# InkTime.net
KiCad netlist of a schematic drawn in EAGLE
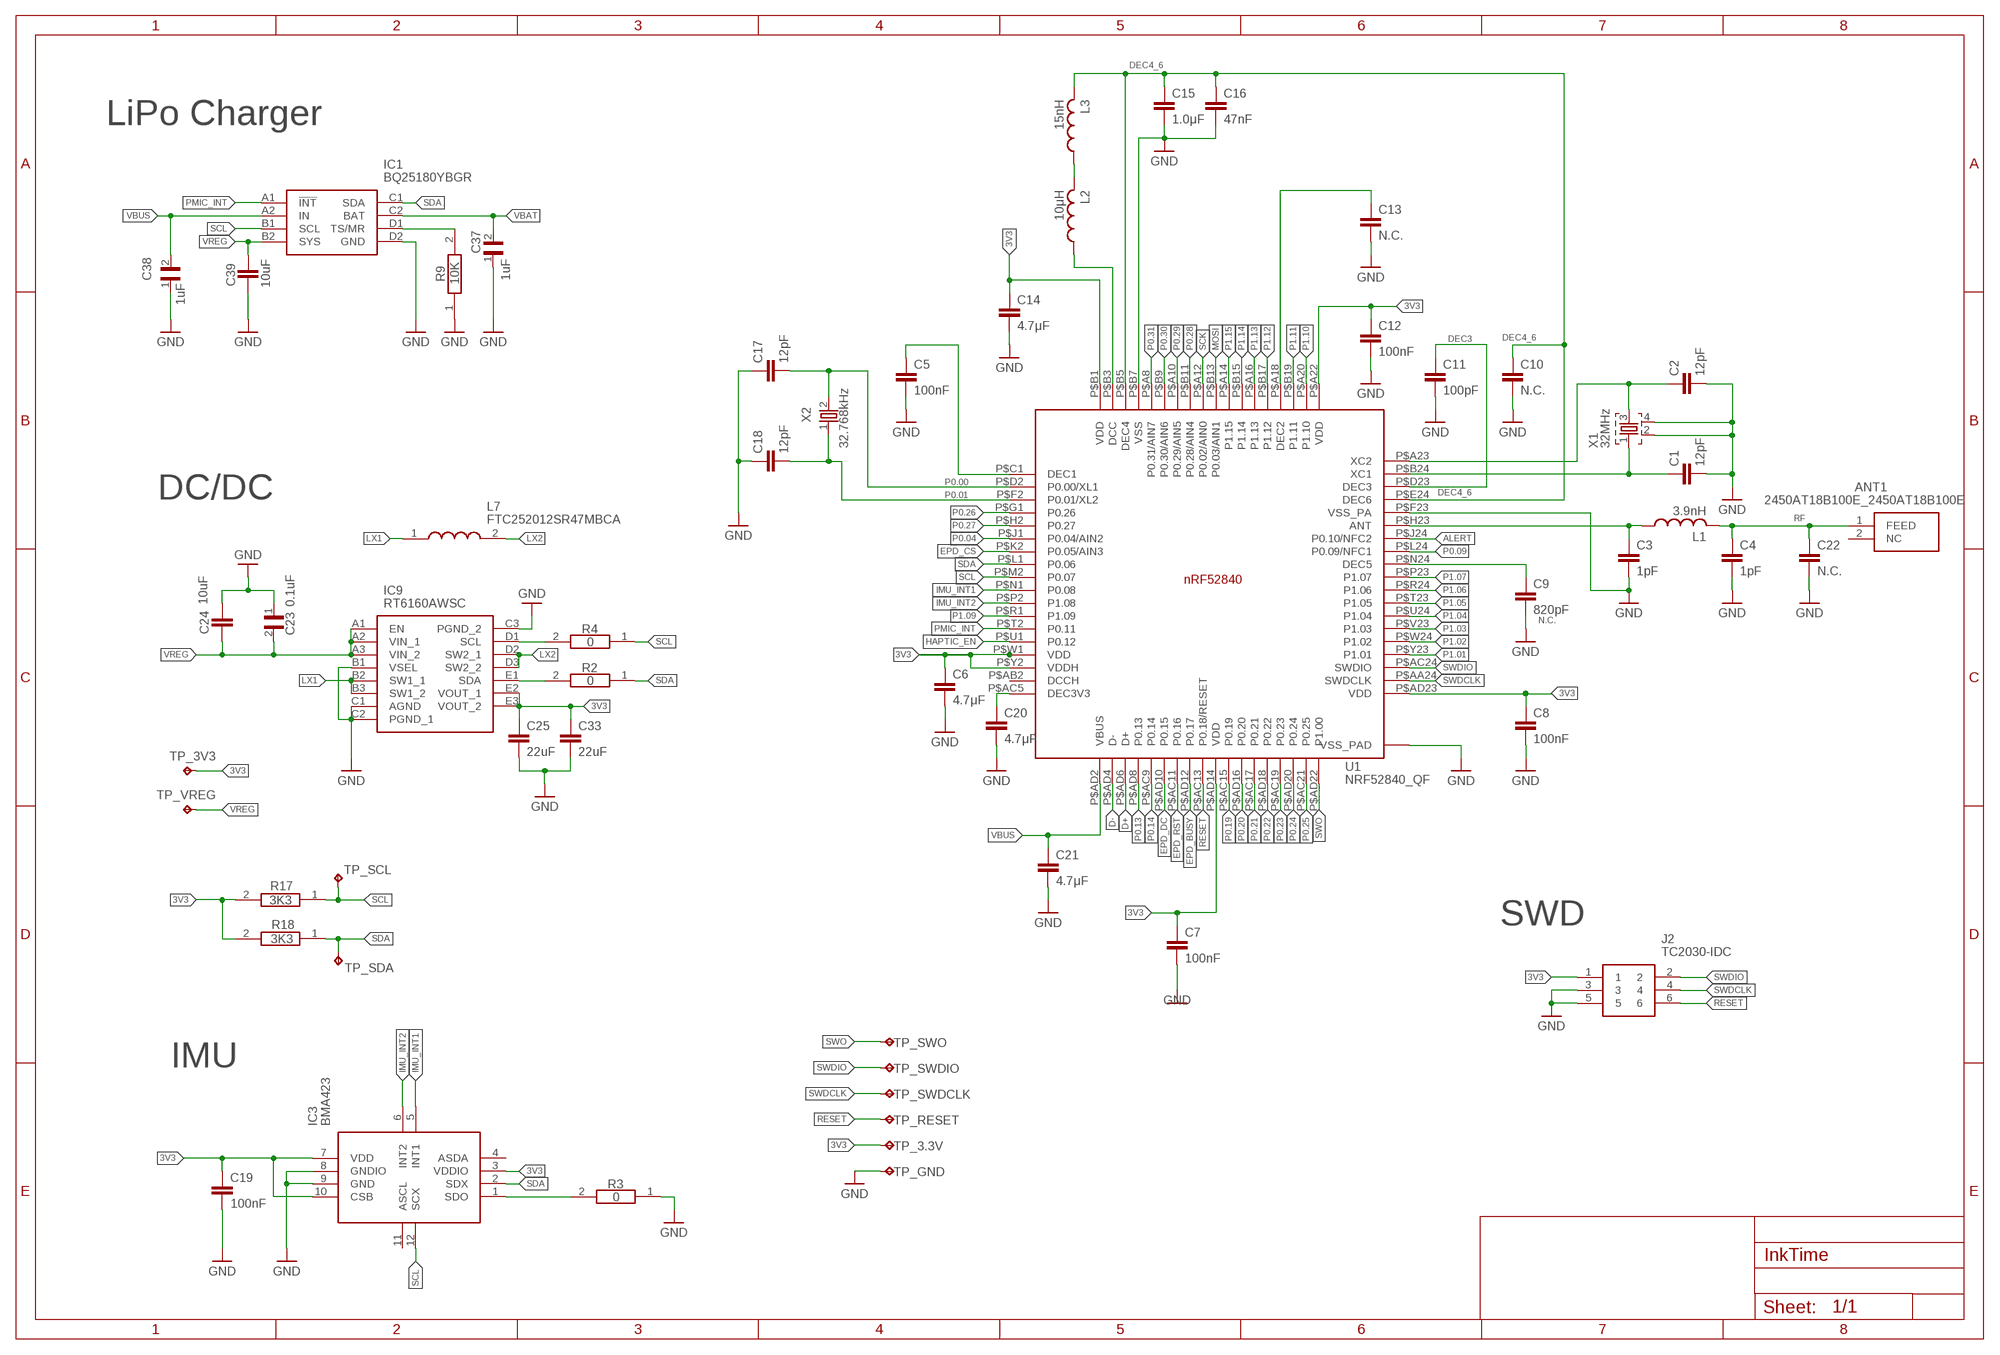
[diagram p0: schematic, sheet 1, part 1 of 2]
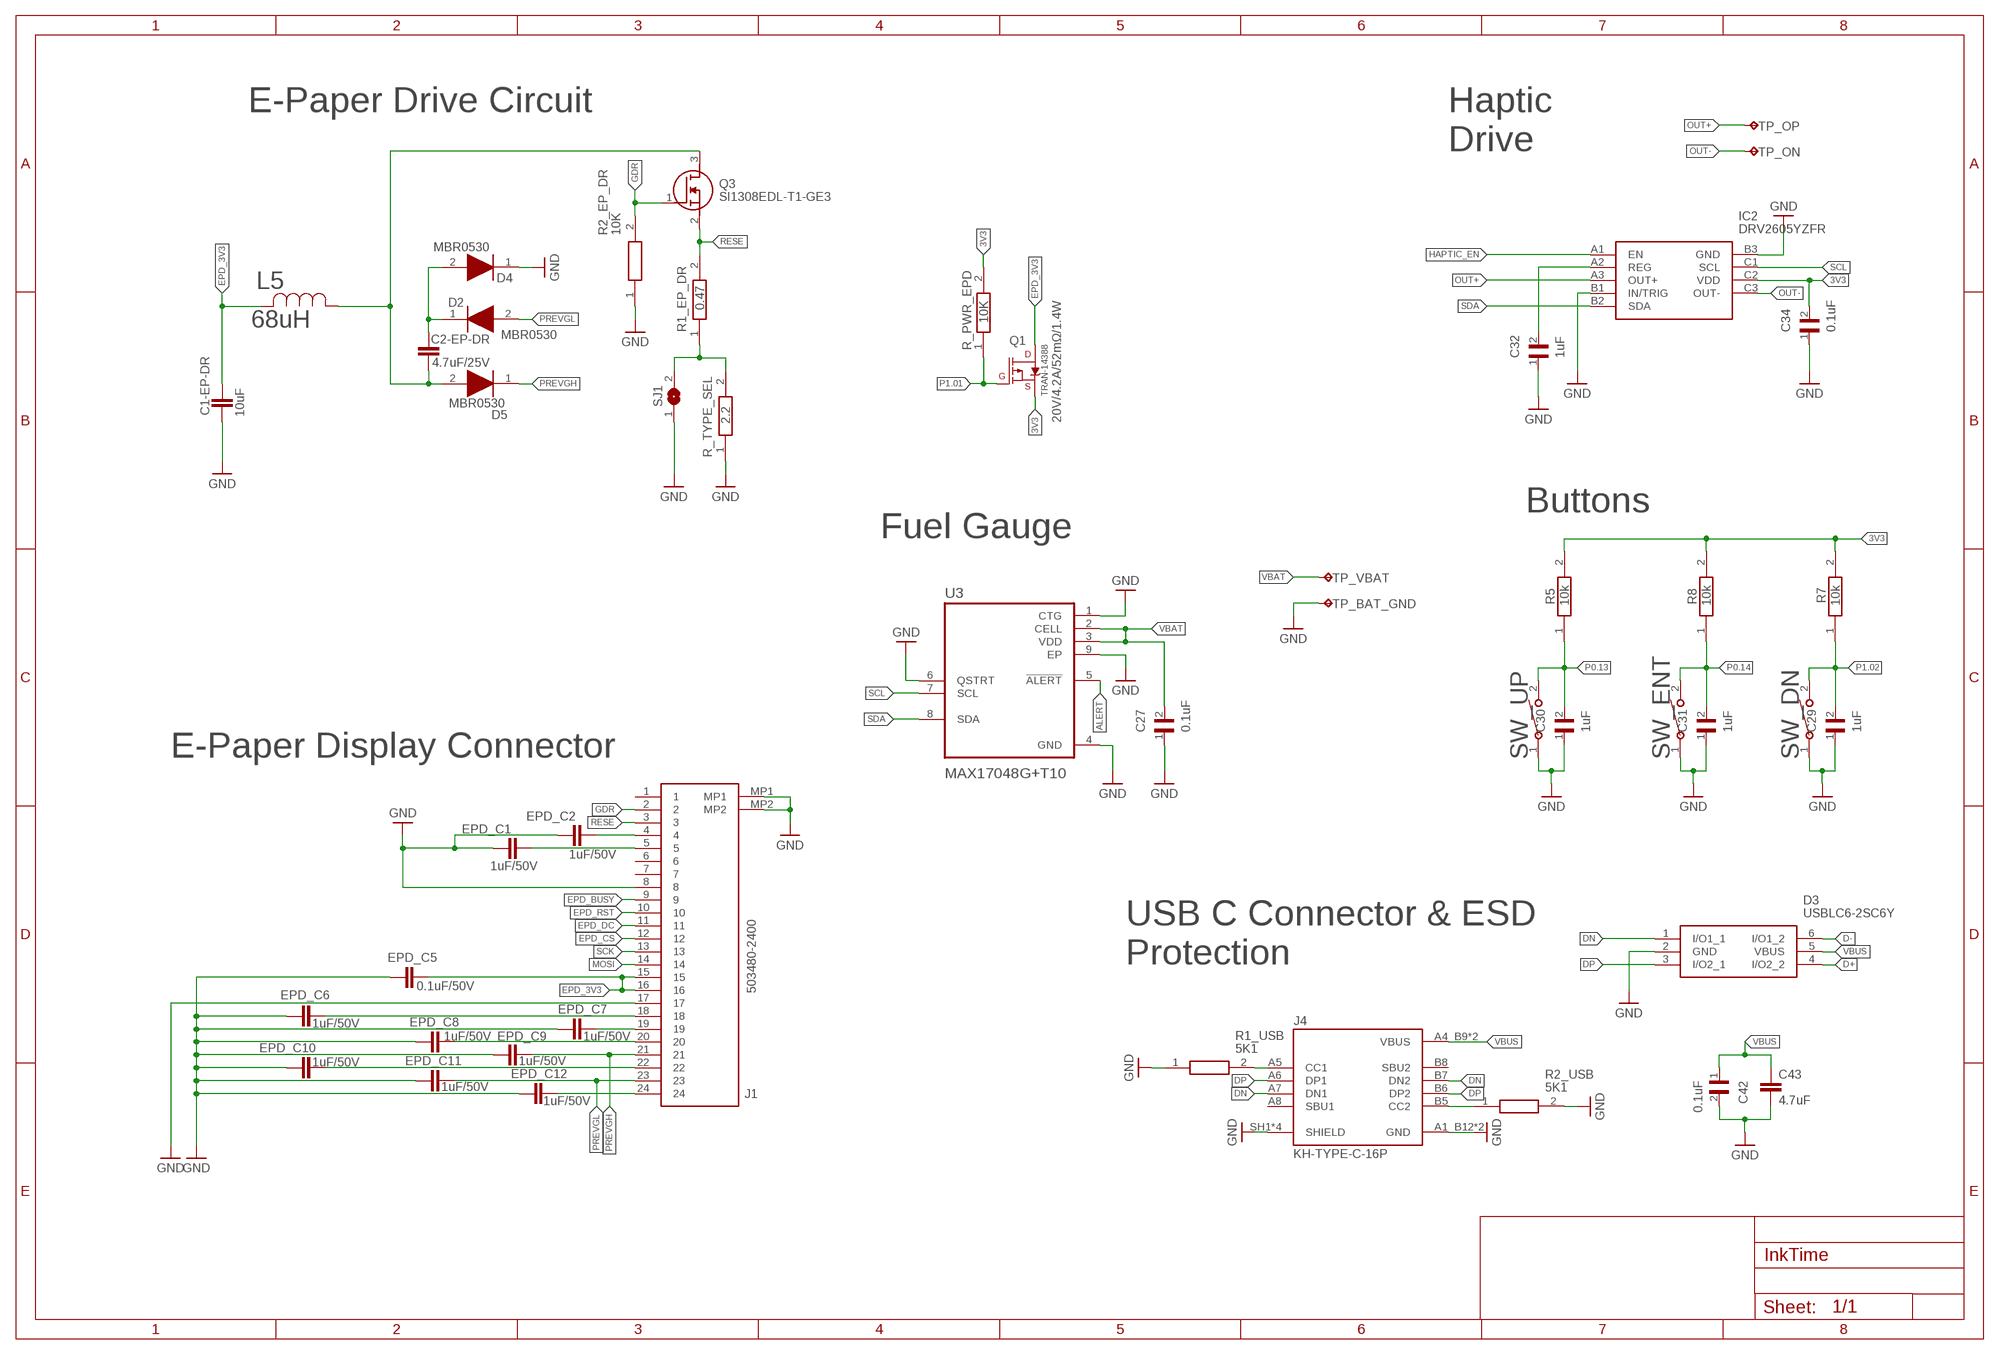
[diagram p1: schematic, sheet 1, part 2 of 2]

(export (version "E")
  (design (tool "Eeschema 10.0.6"))
  (components
    (comp (ref "ANT1")
      (value "2450AT18B100E_2450AT18B100E")
      (footprint "eagle-import:2450AT18B100E_ANTC3216X140N")
      (fields
        (field (name "ARROW_PART_NUMBER") "2450AT18B100E")
        (field (name "MOUSER_PART_NUMBER") "609-2450AT18B100E")
      )
      (libsource (lib "eagle-import") (part "2450AT18B100E_2450AT18B100E"))
    )
    (comp (ref "C1")
      (value "12pF")
      (footprint "eagle-import:NORDIC_NRF_3_RESC0201_L")
      (libsource (lib "eagle-import") (part "NORDIC_NRF_3_CAPACITOR_0201_L"))
    )
    (comp (ref "C1-EP-DR")
      (value "10uF")
      (footprint "eagle-import:NORDIC_NRF_3_RESC0402_L")
      (libsource (lib "eagle-import") (part "NORDIC_NRF_3_CAPACITOR_0402_L"))
    )
    (comp (ref "C2")
      (value "12pF")
      (footprint "eagle-import:NORDIC_NRF_3_RESC0201_L")
      (libsource (lib "eagle-import") (part "NORDIC_NRF_3_CAPACITOR_0201_L"))
    )
    (comp (ref "C2-EP-DR")
      (value "4.7uF/25V")
      (footprint "eagle-import:NORDIC_NRF_3_RESC0402_L")
      (libsource (lib "eagle-import") (part "NORDIC_NRF_3_CAPACITOR_0402_L"))
    )
    (comp (ref "C3")
      (value "1pF")
      (footprint "eagle-import:NORDIC_NRF_3_RESC0201_L")
      (libsource (lib "eagle-import") (part "NORDIC_NRF_3_CAPACITOR_0201_L"))
    )
    (comp (ref "C4")
      (value "1pF")
      (footprint "eagle-import:NORDIC_NRF_3_RESC0201_L")
      (libsource (lib "eagle-import") (part "NORDIC_NRF_3_CAPACITOR_0201_L"))
    )
    (comp (ref "C5")
      (value "100nF")
      (footprint "eagle-import:NORDIC_NRF_3_RESC0201_L")
      (libsource (lib "eagle-import") (part "NORDIC_NRF_3_CAPACITOR_0201_L"))
    )
    (comp (ref "C6")
      (value "4.7μF")
      (footprint "eagle-import:NORDIC_NRF_3_RESC0402_L")
      (libsource (lib "eagle-import") (part "NORDIC_NRF_3_CAPACITOR_0402_L"))
    )
    (comp (ref "C7")
      (value "100nF")
      (footprint "eagle-import:NORDIC_NRF_3_RESC0201_L")
      (libsource (lib "eagle-import") (part "NORDIC_NRF_3_CAPACITOR_0201_L"))
    )
    (comp (ref "C8")
      (value "100nF")
      (footprint "eagle-import:NORDIC_NRF_3_RESC0201_L")
      (libsource (lib "eagle-import") (part "NORDIC_NRF_3_CAPACITOR_0201_L"))
    )
    (comp (ref "C9")
      (value "820pF")
      (footprint "eagle-import:NORDIC_NRF_3_RESC0201_L")
      (fields (field (name "POPULATION") "N.C."))
      (libsource (lib "eagle-import") (part "NORDIC_NRF_3_CAPACITOR_0201_L"))
    )
    (comp (ref "C10")
      (value "N.C.")
      (footprint "eagle-import:NORDIC_NRF_3_RESC0201_L")
      (libsource (lib "eagle-import") (part "NORDIC_NRF_3_CAPACITOR_0201_L"))
    )
    (comp (ref "C11")
      (value "100pF")
      (footprint "eagle-import:NORDIC_NRF_3_RESC0201_L")
      (libsource (lib "eagle-import") (part "NORDIC_NRF_3_CAPACITOR_0201_L"))
    )
    (comp (ref "C12")
      (value "100nF")
      (footprint "eagle-import:NORDIC_NRF_3_RESC0201_L")
      (libsource (lib "eagle-import") (part "NORDIC_NRF_3_CAPACITOR_0201_L"))
    )
    (comp (ref "C13")
      (value "N.C.")
      (footprint "eagle-import:NORDIC_NRF_3_RESC0201_L")
      (libsource (lib "eagle-import") (part "NORDIC_NRF_3_CAPACITOR_0201_L"))
    )
    (comp (ref "C14")
      (value "4.7μF")
      (footprint "eagle-import:NORDIC_NRF_3_RESC0402_L")
      (libsource (lib "eagle-import") (part "NORDIC_NRF_3_CAPACITOR_0402_L"))
    )
    (comp (ref "C15")
      (value "1.0μF")
      (footprint "eagle-import:NORDIC_NRF_3_RESC0402_L")
      (libsource (lib "eagle-import") (part "NORDIC_NRF_3_CAPACITOR_0402_L"))
    )
    (comp (ref "C16")
      (value "47nF")
      (footprint "eagle-import:NORDIC_NRF_3_RESC0201_L")
      (libsource (lib "eagle-import") (part "NORDIC_NRF_3_CAPACITOR_0201_L"))
    )
    (comp (ref "C17")
      (value "12pF")
      (footprint "eagle-import:NORDIC_NRF_3_RESC0201_L")
      (libsource (lib "eagle-import") (part "NORDIC_NRF_3_CAPACITOR_0201_L"))
    )
    (comp (ref "C18")
      (value "12pF")
      (footprint "eagle-import:NORDIC_NRF_3_RESC0201_L")
      (libsource (lib "eagle-import") (part "NORDIC_NRF_3_CAPACITOR_0201_L"))
    )
    (comp (ref "C19")
      (value "100nF")
      (footprint "eagle-import:NORDIC_NRF_3_RESC0201_L")
      (libsource (lib "eagle-import") (part "NORDIC_NRF_3_CAPACITOR_0201_L"))
    )
    (comp (ref "C20")
      (value "4.7μF")
      (footprint "eagle-import:NORDIC_NRF_3_RESC0402_L")
      (libsource (lib "eagle-import") (part "NORDIC_NRF_3_CAPACITOR_0402_L"))
    )
    (comp (ref "C21")
      (value "4.7μF")
      (footprint "eagle-import:NORDIC_NRF_3_RESC0402_L")
      (libsource (lib "eagle-import") (part "NORDIC_NRF_3_CAPACITOR_0402_L"))
    )
    (comp (ref "C22")
      (value "N.C.")
      (footprint "eagle-import:NORDIC_NRF_3_RESC0201_L")
      (libsource (lib "eagle-import") (part "NORDIC_NRF_3_CAPACITOR_0201_L"))
    )
    (comp (ref "C23")
      (value "0.1uF")
      (footprint "eagle-import:GRM011R60J152KE01L_2_CAPC0201X13N")
      (fields (field (name "MF") "Murata") (field (name "MP") "GRM011R60J152KE01L"))
      (libsource (lib "eagle-import") (part "GRM011R60J152KE01L_2_GRM011R60J152KE01L"))
    )
    (comp (ref "C24")
      (value "10uF")
      (footprint "eagle-import:NORDIC_NRF_3_RESC0402_L")
      (libsource (lib "eagle-import") (part "NORDIC_NRF_3_CAPACITOR_0402_L"))
    )
    (comp (ref "C25")
      (value "22uF")
      (footprint "eagle-import:NORDIC_NRF_3_RESC0402_L")
      (libsource (lib "eagle-import") (part "NORDIC_NRF_3_CAPACITOR_0402_L"))
    )
    (comp (ref "C27")
      (value "0.1uF")
      (footprint "eagle-import:GRM011R60J152KE01L_2_CAPC0201X13N")
      (fields (field (name "MF") "Murata") (field (name "MP") "GRM011R60J152KE01L"))
      (libsource (lib "eagle-import") (part "GRM011R60J152KE01L_2_GRM011R60J152KE01L"))
    )
    (comp (ref "C29")
      (value "1uF")
      (footprint "eagle-import:GRM011R60J152KE01L_2_CAPC0201X13N")
      (fields (field (name "MF") "Murata") (field (name "MP") "GRM011R60J152KE01L"))
      (libsource (lib "eagle-import") (part "GRM011R60J152KE01L_2_GRM011R60J152KE01L"))
    )
    (comp (ref "C30")
      (value "1uF")
      (footprint "eagle-import:GRM011R60J152KE01L_2_CAPC0201X13N")
      (fields (field (name "MF") "Murata") (field (name "MP") "GRM011R60J152KE01L"))
      (libsource (lib "eagle-import") (part "GRM011R60J152KE01L_2_GRM011R60J152KE01L"))
    )
    (comp (ref "C31")
      (value "1uF")
      (footprint "eagle-import:GRM011R60J152KE01L_2_CAPC0201X13N")
      (fields (field (name "MF") "Murata") (field (name "MP") "GRM011R60J152KE01L"))
      (libsource (lib "eagle-import") (part "GRM011R60J152KE01L_2_GRM011R60J152KE01L"))
    )
    (comp (ref "C32")
      (value "1uF")
      (footprint "eagle-import:GRM011R60J152KE01L_2_CAPC0201X13N")
      (fields (field (name "MF") "Murata") (field (name "MP") "GRM011R60J152KE01L"))
      (libsource (lib "eagle-import") (part "GRM011R60J152KE01L_2_GRM011R60J152KE01L"))
    )
    (comp (ref "C33")
      (value "22uF")
      (footprint "eagle-import:NORDIC_NRF_3_RESC0402_L")
      (libsource (lib "eagle-import") (part "NORDIC_NRF_3_CAPACITOR_0402_L"))
    )
    (comp (ref "C34")
      (value "0.1uF")
      (footprint "eagle-import:GRM011R60J152KE01L_2_CAPC0201X13N")
      (fields (field (name "MF") "Murata") (field (name "MP") "GRM011R60J152KE01L"))
      (libsource (lib "eagle-import") (part "GRM011R60J152KE01L_2_GRM011R60J152KE01L"))
    )
    (comp (ref "C37")
      (value "1uF")
      (footprint "eagle-import:GRM011R60J152KE01L_2_CAPC0201X13N")
      (fields (field (name "MF") "Murata") (field (name "MP") "GRM011R60J152KE01L"))
      (libsource (lib "eagle-import") (part "GRM011R60J152KE01L_2_GRM011R60J152KE01L"))
    )
    (comp (ref "C38")
      (value "1uF")
      (footprint "eagle-import:GRM011R60J152KE01L_2_CAPC0201X13N")
      (fields (field (name "MF") "Murata") (field (name "MP") "GRM011R60J152KE01L"))
      (libsource (lib "eagle-import") (part "GRM011R60J152KE01L_2_GRM011R60J152KE01L"))
    )
    (comp (ref "C39")
      (value "10uF")
      (footprint "eagle-import:NORDIC_NRF_3_RESC0402_L")
      (libsource (lib "eagle-import") (part "NORDIC_NRF_3_CAPACITOR_0402_L"))
    )
    (comp (ref "C42")
      (value "0.1uF")
      (footprint "eagle-import:GRM011R60J152KE01L_2_CAPC0201X13N")
      (fields (field (name "MF") "Murata") (field (name "MP") "GRM011R60J152KE01L"))
      (libsource (lib "eagle-import") (part "GRM011R60J152KE01L_2_GRM011R60J152KE01L"))
    )
    (comp (ref "C43")
      (value "4.7uF")
      (footprint "eagle-import:NORDIC_NRF_3_RESC0402_L")
      (libsource (lib "eagle-import") (part "NORDIC_NRF_3_CAPACITOR_0402_L"))
    )
    (comp (ref "D2")
      (value "MBR0530")
      (footprint "eagle-import:ESP32_C6_LIBRARY_5_SOD3716X135N")
      (fields (field (name "MF") "ON Semiconductor"))
      (libsource (lib "eagle-import") (part "ESP32_C6_LIBRARY_5_MBR0530"))
    )
    (comp (ref "D3")
      (value "USBLC6-2SC6Y")
      (footprint "eagle-import:ESP32_C6_LIBRARY_3_SOT95P280X145-6N")
      (fields (field (name "MF") "STMicroelectronics"))
      (libsource (lib "eagle-import") (part "ESP32_C6_LIBRARY_3_USBLC6-2SC6Y"))
    )
    (comp (ref "D4")
      (value "MBR0530")
      (footprint "eagle-import:ESP32_C6_LIBRARY_5_SOD3716X135N")
      (fields (field (name "MF") "ON Semiconductor"))
      (libsource (lib "eagle-import") (part "ESP32_C6_LIBRARY_5_MBR0530"))
    )
    (comp (ref "D5")
      (value "MBR0530")
      (footprint "eagle-import:ESP32_C6_LIBRARY_5_SOD3716X135N")
      (fields (field (name "MF") "ON Semiconductor"))
      (libsource (lib "eagle-import") (part "ESP32_C6_LIBRARY_5_MBR0530"))
    )
    (comp (ref "EPD_C1")
      (value "1uF/50V")
      (footprint "eagle-import:NORDIC_NRF_3_RESC0402_L")
      (libsource (lib "eagle-import") (part "NORDIC_NRF_3_CAPACITOR_0402_L"))
    )
    (comp (ref "EPD_C2")
      (value "1uF/50V")
      (footprint "eagle-import:NORDIC_NRF_3_RESC0402_L")
      (libsource (lib "eagle-import") (part "NORDIC_NRF_3_CAPACITOR_0402_L"))
    )
    (comp (ref "EPD_C5")
      (value "0.1uF/50V")
      (footprint "eagle-import:NORDIC_NRF_3_RESC0201_L")
      (libsource (lib "eagle-import") (part "NORDIC_NRF_3_CAPACITOR_0201_L"))
    )
    (comp (ref "EPD_C6")
      (value "1uF/50V")
      (footprint "eagle-import:NORDIC_NRF_3_RESC0402_L")
      (libsource (lib "eagle-import") (part "NORDIC_NRF_3_CAPACITOR_0402_L"))
    )
    (comp (ref "EPD_C7")
      (value "1uF/50V")
      (footprint "eagle-import:NORDIC_NRF_3_RESC0402_L")
      (libsource (lib "eagle-import") (part "NORDIC_NRF_3_CAPACITOR_0402_L"))
    )
    (comp (ref "EPD_C8")
      (value "1uF/50V")
      (footprint "eagle-import:NORDIC_NRF_3_RESC0402_L")
      (libsource (lib "eagle-import") (part "NORDIC_NRF_3_CAPACITOR_0402_L"))
    )
    (comp (ref "EPD_C9")
      (value "1uF/50V")
      (footprint "eagle-import:NORDIC_NRF_3_RESC0402_L")
      (libsource (lib "eagle-import") (part "NORDIC_NRF_3_CAPACITOR_0402_L"))
    )
    (comp (ref "EPD_C10")
      (value "1uF/50V")
      (footprint "eagle-import:NORDIC_NRF_3_RESC0402_L")
      (libsource (lib "eagle-import") (part "NORDIC_NRF_3_CAPACITOR_0402_L"))
    )
    (comp (ref "EPD_C11")
      (value "1uF/50V")
      (footprint "eagle-import:NORDIC_NRF_3_RESC0402_L")
      (libsource (lib "eagle-import") (part "NORDIC_NRF_3_CAPACITOR_0402_L"))
    )
    (comp (ref "EPD_C12")
      (value "1uF/50V")
      (footprint "eagle-import:NORDIC_NRF_3_RESC0402_L")
      (libsource (lib "eagle-import") (part "NORDIC_NRF_3_CAPACITOR_0402_L"))
    )
    (comp (ref "IC1")
      (value "BQ25180YBGR")
      (footprint "eagle-import:BQ25180YBGR_BGA8C40P2X4_100X155X50")
      (fields (field (name "MOUSER_PART_NUMBER") "595-BQ25180YBGR"))
      (libsource (lib "eagle-import") (part "BQ25180YBGR_BQ25180YBGR"))
    )
    (comp (ref "IC2")
      (value "DRV2605YZFR")
      (footprint "eagle-import:DRV2605YZFR_BGA9C50P3X3_144X144X62")
      (libsource (lib "eagle-import") (part "DRV2605YZFR_DRV2605YZFR"))
    )
    (comp (ref "IC3")
      (value "BMA423")
      (footprint "eagle-import:BMA423_BMA423")
      (fields (field (name "MOUSER_PART_NUMBER") "262-BMA423"))
      (libsource (lib "eagle-import") (part "BMA423_BMA423"))
    )
    (comp (ref "IC9")
      (value "RT6160AWSC")
      (footprint "eagle-import:RT6160AWSC_BGA15C40P3X5_140X230X60")
      (fields (field (name "MOUSER_PART_NUMBER") "835-RT6160AWSC"))
      (libsource (lib "eagle-import") (part "RT6160AWSC_RT6160AWSC"))
    )
    (comp (ref "J1")
      (value "503480-2400")
      (footprint "eagle-import:503480-2400_5034802400")
      (fields (field (name "MOUSER_PART_NUMBER") "538-503480-2400"))
      (libsource (lib "eagle-import") (part "503480-2400_503480-2400"))
    )
    (comp (ref "J2")
      (value "TC2030-IDC")
      (footprint "eagle-import:TC2030-IDC_TC2030IDC")
      (libsource (lib "eagle-import") (part "TC2030-IDC_TC2030-IDC"))
    )
    (comp (ref "J4")
      (value "KH-TYPE-C-16P")
      (footprint "eagle-import:KH-TYPE-C-16P_KINGHELM_KH-TYPE-C-16P")
      (fields (field (name "MF") "kinghelm"))
      (libsource (lib "eagle-import") (part "KH-TYPE-C-16P_KH-TYPE-C-16P"))
    )
    (comp (ref "L1")
      (value "3.9nH")
      (footprint "eagle-import:NORDIC_NRF_2_RESC0402_L")
      (libsource (lib "eagle-import") (part "NORDIC_NRF_2_INDUCTOR_0402_L"))
    )
    (comp (ref "L2")
      (value "10μH")
      (footprint "eagle-import:NORDIC_NRF_2_RESC0402_L")
      (libsource (lib "eagle-import") (part "NORDIC_NRF_2_INDUCTOR_0402_L"))
    )
    (comp (ref "L3")
      (value "15nH")
      (footprint "eagle-import:NORDIC_NRF_2_RESC0402_L")
      (libsource (lib "eagle-import") (part "NORDIC_NRF_2_INDUCTOR_0402_L"))
    )
    (comp (ref "L5")
      (value "68uH")
      (footprint "eagle-import:ESP32_C6_LIBRARY_2_IND_4828-WE-TPC_WRE")
      (fields
        (field (name "MANUFACTURER_PART_NUMBER") "744043680")
        (field (name "COPYRIGHT") "Copyright (C) 2024 Ultra Librarian. All rights reserved.")
      )
      (libsource (lib "eagle-import") (part "ESP32_C6_LIBRARY_2_744043680IND_4828-WE-TPC_WRE"))
    )
    (comp (ref "L7")
      (value "FTC252012SR47MBCA")
      (footprint "eagle-import:MLP2016SR47MT0S1_INDC2016X100N")
      (libsource (lib "eagle-import") (part "MLP2016SR47MT0S1_FTC252012SR47MBCA"))
    )
    (comp (ref "Q1")
      (value "20V/4.2A/52mΩ/1.4W")
      (footprint "eagle-import:ESP32_C6_LIBRARY_4_ESP32_C6_LIBRARY_4_ESP32_C6_LIBRARY_4_ESP32_C6_LIBRARY_4_ESP32_WROVER_SPARKFUN-DISCRETESEMI_SOT23-3")
      (fields (field (name "PROD_ID") "TRAN-14388"))
      (libsource (lib "eagle-import") (part "ESP32_C6_LIBRARY_4_ESP32_WROVER_SPARKFUN-DISCRETESEMI_MOSFET_PCH-DMG2305UX-7"))
    )
    (comp (ref "Q3")
      (value "SI1308EDL-T1-GE3")
      (footprint "eagle-import:ESP32_C6_LIBRARY_6_SOT65P210X110-3N")
      (fields (field (name "MF") "Vishay Siliconix"))
      (libsource (lib "eagle-import") (part "ESP32_C6_LIBRARY_6_SI1308EDL-T1-GE3"))
    )
    (comp (ref "R1_EP_DR")
      (value "0.47")
      (footprint "eagle-import:ERA-1AEB3401C_0201")
      (libsource (lib "eagle-import") (part "ERA-1AEB3401C_CPF0201D7K68C1"))
    )
    (comp (ref "R1_USB")
      (value "5K1")
      (footprint "eagle-import:ERA-1AEB3401C_0201")
      (libsource (lib "eagle-import") (part "ERA-1AEB3401C_CPF0201D7K68C1"))
    )
    (comp (ref "R2")
      (value "0")
      (footprint "eagle-import:ERA-1AEB3401C_0201")
      (libsource (lib "eagle-import") (part "ERA-1AEB3401C_CPF0201D7K68C1"))
    )
    (comp (ref "R2_EP_DR")
      (value "10K")
      (footprint "eagle-import:ERA-1AEB3401C_0201")
      (libsource (lib "eagle-import") (part "ERA-1AEB3401C_CPF0201D7K68C1"))
    )
    (comp (ref "R2_USB")
      (value "5K1")
      (footprint "eagle-import:ERA-1AEB3401C_0201")
      (libsource (lib "eagle-import") (part "ERA-1AEB3401C_CPF0201D7K68C1"))
    )
    (comp (ref "R3")
      (value "0")
      (footprint "eagle-import:ERA-1AEB3401C_0201")
      (libsource (lib "eagle-import") (part "ERA-1AEB3401C_CPF0201D7K68C1"))
    )
    (comp (ref "R4")
      (value "0")
      (footprint "eagle-import:ERA-1AEB3401C_0201")
      (libsource (lib "eagle-import") (part "ERA-1AEB3401C_CPF0201D7K68C1"))
    )
    (comp (ref "R5")
      (value "10k")
      (footprint "eagle-import:ERA-1AEB3401C_0201")
      (libsource (lib "eagle-import") (part "ERA-1AEB3401C_CPF0201D7K68C1"))
    )
    (comp (ref "R7")
      (value "10k")
      (footprint "eagle-import:ERA-1AEB3401C_0201")
      (libsource (lib "eagle-import") (part "ERA-1AEB3401C_CPF0201D7K68C1"))
    )
    (comp (ref "R8")
      (value "10k")
      (footprint "eagle-import:ERA-1AEB3401C_0201")
      (libsource (lib "eagle-import") (part "ERA-1AEB3401C_CPF0201D7K68C1"))
    )
    (comp (ref "R9")
      (value "10K")
      (footprint "eagle-import:ERA-1AEB3401C_0201")
      (libsource (lib "eagle-import") (part "ERA-1AEB3401C_CPF0201D7K68C1"))
    )
    (comp (ref "R17")
      (value "3K3")
      (footprint "eagle-import:ERA-1AEB3401C_0201")
      (libsource (lib "eagle-import") (part "ERA-1AEB3401C_CPF0201D7K68C1"))
    )
    (comp (ref "R18")
      (value "3K3")
      (footprint "eagle-import:ERA-1AEB3401C_0201")
      (libsource (lib "eagle-import") (part "ERA-1AEB3401C_CPF0201D7K68C1"))
    )
    (comp (ref "R_PWR_EPD")
      (value "10K")
      (footprint "eagle-import:ERA-1AEB3401C_0201")
      (libsource (lib "eagle-import") (part "ERA-1AEB3401C_CPF0201D7K68C1"))
    )
    (comp (ref "R_TYPE_SEL")
      (value "2.2")
      (footprint "eagle-import:ERA-1AEB3401C_0201")
      (libsource (lib "eagle-import") (part "ERA-1AEB3401C_CPF0201D7K68C1"))
    )
    (comp (ref "SJ1")
      (value "ESP32_C6_LIBRARY_7_JUMPER_SJ")
      (footprint "eagle-import:ESP32_C6_LIBRARY_7_JUMPER_SJ")
      (libsource (lib "eagle-import") (part "ESP32_C6_LIBRARY_7_JUMPER_SJ"))
    )
    (comp (ref "SW_DN")
      (value "2025-10-22_07-23-44_LIBRARY_EVP-AKE31ASW_EVP-AKE31A_PAN")
      (footprint "eagle-import:2025-10-22_07-23-44_LIBRARY_SW_EVP-AKE31A_PAN")
      (fields
        (field (name "MANUFACTURER_PART_NUMBER") "EVP-AKE31A")
        (field (name "COPYRIGHT") "Copyright (C) 2025 Ultra Librarian. All rights reserved.")
      )
      (libsource (lib "eagle-import") (part "2025-10-22_07-23-44_LIBRARY_EVP-AKE31ASW_EVP-AKE31A_PAN"))
    )
    (comp (ref "SW_ENT")
      (value "2025-10-22_07-23-44_LIBRARY_EVP-AKE31ASW_EVP-AKE31A_PAN")
      (footprint "eagle-import:2025-10-22_07-23-44_LIBRARY_SW_EVP-AKE31A_PAN")
      (fields
        (field (name "MANUFACTURER_PART_NUMBER") "EVP-AKE31A")
        (field (name "COPYRIGHT") "Copyright (C) 2025 Ultra Librarian. All rights reserved.")
      )
      (libsource (lib "eagle-import") (part "2025-10-22_07-23-44_LIBRARY_EVP-AKE31ASW_EVP-AKE31A_PAN"))
    )
    (comp (ref "SW_UP")
      (value "2025-10-22_07-23-44_LIBRARY_EVP-AKE31ASW_EVP-AKE31A_PAN")
      (footprint "eagle-import:2025-10-22_07-23-44_LIBRARY_SW_EVP-AKE31A_PAN")
      (fields
        (field (name "MANUFACTURER_PART_NUMBER") "EVP-AKE31A")
        (field (name "COPYRIGHT") "Copyright (C) 2025 Ultra Librarian. All rights reserved.")
      )
      (libsource (lib "eagle-import") (part "2025-10-22_07-23-44_LIBRARY_EVP-AKE31ASW_EVP-AKE31A_PAN"))
    )
    (comp (ref "TP_3.3V")
      (value "HECTOR_WATCH_1_TPTP20R")
      (footprint "eagle-import:HECTOR_WATCH_1_TP20R")
      (libsource (lib "eagle-import") (part "HECTOR_WATCH_1_TPTP20R"))
    )
    (comp (ref "TP_3V3")
      (value "HECTOR_WATCH_1_TPTP20R")
      (footprint "eagle-import:HECTOR_WATCH_1_TP20R")
      (libsource (lib "eagle-import") (part "HECTOR_WATCH_1_TPTP20R"))
    )
    (comp (ref "TP_BAT_GND")
      (value "HECTOR_WATCH_1_TPTP20R")
      (footprint "eagle-import:HECTOR_WATCH_1_TP20R")
      (libsource (lib "eagle-import") (part "HECTOR_WATCH_1_TPTP20R"))
    )
    (comp (ref "TP_GND")
      (value "HECTOR_WATCH_1_TPTP20R")
      (footprint "eagle-import:HECTOR_WATCH_1_TP20R")
      (libsource (lib "eagle-import") (part "HECTOR_WATCH_1_TPTP20R"))
    )
    (comp (ref "TP_ON")
      (value "HECTOR_WATCH_1_TPTP20R")
      (footprint "eagle-import:HECTOR_WATCH_1_TP20R")
      (libsource (lib "eagle-import") (part "HECTOR_WATCH_1_TPTP20R"))
    )
    (comp (ref "TP_OP")
      (value "HECTOR_WATCH_1_TPTP20R")
      (footprint "eagle-import:HECTOR_WATCH_1_TP20R")
      (libsource (lib "eagle-import") (part "HECTOR_WATCH_1_TPTP20R"))
    )
    (comp (ref "TP_RESET")
      (value "HECTOR_WATCH_1_TPTP20R")
      (footprint "eagle-import:HECTOR_WATCH_1_TP20R")
      (libsource (lib "eagle-import") (part "HECTOR_WATCH_1_TPTP20R"))
    )
    (comp (ref "TP_SCL")
      (value "HECTOR_WATCH_1_TPTP20R")
      (footprint "eagle-import:HECTOR_WATCH_1_TP20R")
      (libsource (lib "eagle-import") (part "HECTOR_WATCH_1_TPTP20R"))
    )
    (comp (ref "TP_SDA")
      (value "HECTOR_WATCH_1_TPTP20R")
      (footprint "eagle-import:HECTOR_WATCH_1_TP20R")
      (libsource (lib "eagle-import") (part "HECTOR_WATCH_1_TPTP20R"))
    )
    (comp (ref "TP_SWDCLK")
      (value "HECTOR_WATCH_1_TPTP20R")
      (footprint "eagle-import:HECTOR_WATCH_1_TP20R")
      (libsource (lib "eagle-import") (part "HECTOR_WATCH_1_TPTP20R"))
    )
    (comp (ref "TP_SWDIO")
      (value "HECTOR_WATCH_1_TPTP20R")
      (footprint "eagle-import:HECTOR_WATCH_1_TP20R")
      (libsource (lib "eagle-import") (part "HECTOR_WATCH_1_TPTP20R"))
    )
    (comp (ref "TP_SWO")
      (value "HECTOR_WATCH_1_TPTP20R")
      (footprint "eagle-import:HECTOR_WATCH_1_TP20R")
      (libsource (lib "eagle-import") (part "HECTOR_WATCH_1_TPTP20R"))
    )
    (comp (ref "TP_VBAT")
      (value "HECTOR_WATCH_1_TPTP20R")
      (footprint "eagle-import:HECTOR_WATCH_1_TP20R")
      (libsource (lib "eagle-import") (part "HECTOR_WATCH_1_TPTP20R"))
    )
    (comp (ref "TP_VREG")
      (value "HECTOR_WATCH_1_TPTP20R")
      (footprint "eagle-import:HECTOR_WATCH_1_TP20R")
      (libsource (lib "eagle-import") (part "HECTOR_WATCH_1_TPTP20R"))
    )
    (comp (ref "U1")
      (value "NRF52840_QF")
      (footprint "eagle-import:NORDIC_NRF_4_AQFN50P700X700X85_HS-74N")
      (libsource (lib "eagle-import") (part "NORDIC_NRF_4_NRF52840_QF"))
    )
    (comp (ref "U3")
      (value "MAX17048G+T10")
      (footprint "eagle-import:ESP32_C6_LIBRARY_SON50P200X200X80-9N")
      (fields (field (name "MF") "Analog Devices"))
      (libsource (lib "eagle-import") (part "ESP32_C6_LIBRARY_MAX17048G+T10"))
    )
    (comp (ref "X1")
      (value "32MHz")
      (footprint "eagle-import:NORDIC_NRF_BT-XTAL_2016_N")
      (libsource (lib "eagle-import") (part "NORDIC_NRF_XTAL_32MHZ"))
    )
    (comp (ref "X2")
      (value "32.768kHz")
      (footprint "eagle-import:NORDIC_NRF_1_XTAL_3215_N")
      (libsource (lib "eagle-import") (part "NORDIC_NRF_1_XTAL_32KHZ"))
    )
  )
  (nets
    (net (code "1") (name "/DEC3") (class "Default")
      (node (ref "C11") (pin "1") (pinfunction "1_1") (pintype "passive"))
      (node (ref "U1") (pin "P$D23") (pinfunction "DEC3_P$D23") (pintype "bidirectional"))
    )
    (net (code "2") (name "/DEC4_6") (class "Default")
      (node (ref "C10") (pin "1") (pinfunction "1_1") (pintype "passive"))
      (node (ref "C15") (pin "1") (pinfunction "1_1") (pintype "passive"))
      (node (ref "C16") (pin "1") (pinfunction "1_1") (pintype "passive"))
      (node (ref "L3") (pin "2") (pinfunction "2_2") (pintype "passive"))
      (node (ref "U1") (pin "P$B5") (pinfunction "DEC4_P$B5") (pintype "power_in"))
      (node (ref "U1") (pin "P$E24") (pinfunction "DEC6_P$E24") (pintype "bidirectional"))
    )
    (net (code "3") (name "/P0.00") (class "Default")
      (node (ref "C17") (pin "2") (pinfunction "2_2") (pintype "passive"))
      (node (ref "U1") (pin "P$D2") (pinfunction "P0.00/XL1_P$D2") (pintype "bidirectional"))
      (node (ref "X2") (pin "2") (pinfunction "2_2") (pintype "passive"))
    )
    (net (code "4") (name "/P0.01") (class "Default")
      (node (ref "C18") (pin "2") (pinfunction "2_2") (pintype "passive"))
      (node (ref "U1") (pin "P$F2") (pinfunction "P0.01/XL2_P$F2") (pintype "bidirectional"))
      (node (ref "X2") (pin "1") (pinfunction "1_1") (pintype "passive"))
    )
    (net (code "5") (name "/RF") (class "Default")
      (node (ref "ANT1") (pin "1") (pinfunction "FEED_1") (pintype "input"))
      (node (ref "C22") (pin "1") (pinfunction "1_1") (pintype "passive"))
      (node (ref "C4") (pin "1") (pinfunction "1_1") (pintype "passive"))
      (node (ref "L1") (pin "2") (pinfunction "2_2") (pintype "passive"))
    )
    (net (code "6") (name "3V3") (class "Default")
      (node (ref "C12") (pin "1") (pinfunction "1_1") (pintype "passive"))
      (node (ref "C14") (pin "1") (pinfunction "1_1") (pintype "passive"))
      (node (ref "C19") (pin "2") (pinfunction "2_2") (pintype "passive"))
      (node (ref "C25") (pin "1") (pinfunction "1_1") (pintype "passive"))
      (node (ref "C33") (pin "1") (pinfunction "1_1") (pintype "passive"))
      (node (ref "C34") (pin "2") (pinfunction "2_2") (pintype "passive"))
      (node (ref "C6") (pin "1") (pinfunction "1_1") (pintype "passive"))
      (node (ref "C7") (pin "1") (pinfunction "1_1") (pintype "passive"))
      (node (ref "C8") (pin "1") (pinfunction "1_1") (pintype "passive"))
      (node (ref "IC2") (pin "C2") (pinfunction "VDD_C2") (pintype "bidirectional"))
      (node (ref "IC3") (pin "10") (pinfunction "CSB_10") (pintype "bidirectional"))
      (node (ref "IC3") (pin "3") (pinfunction "VDDIO_3") (pintype "bidirectional"))
      (node (ref "IC3") (pin "7") (pinfunction "VDD_7") (pintype "bidirectional"))
      (node (ref "IC9") (pin "E2") (pinfunction "VOUT_1_E2") (pintype "bidirectional"))
      (node (ref "IC9") (pin "E3") (pinfunction "VOUT_2_E3") (pintype "bidirectional"))
      (node (ref "J2") (pin "1") (pinfunction "1_1") (pintype "bidirectional"))
      (node (ref "Q1") (pin "2") (pinfunction "S_2") (pintype "bidirectional"))
      (node (ref "R17") (pin "2") (pinfunction "2_2") (pintype "bidirectional"))
      (node (ref "R18") (pin "2") (pinfunction "2_2") (pintype "bidirectional"))
      (node (ref "R5") (pin "2") (pinfunction "2_2") (pintype "bidirectional"))
      (node (ref "R7") (pin "2") (pinfunction "2_2") (pintype "bidirectional"))
      (node (ref "R8") (pin "2") (pinfunction "2_2") (pintype "bidirectional"))
      (node (ref "R_PWR_EPD") (pin "2") (pinfunction "2_2") (pintype "bidirectional"))
      (node (ref "TP_3.3V") (pin "TP") (pinfunction "TP_TP") (pintype "input"))
      (node (ref "TP_3V3") (pin "TP") (pinfunction "TP_TP") (pintype "input"))
      (node (ref "U1") (pin "P$A22") (pinfunction "VDD_P$A22") (pintype "power_in"))
      (node (ref "U1") (pin "P$AD14") (pinfunction "VDD_P$AD14") (pintype "power_in"))
      (node (ref "U1") (pin "P$AD23") (pinfunction "VDD_P$AD23") (pintype "power_in"))
      (node (ref "U1") (pin "P$B1") (pinfunction "VDD_P$B1") (pintype "power_in"))
      (node (ref "U1") (pin "P$W1") (pinfunction "VDD_P$W1") (pintype "power_in"))
      (node (ref "U1") (pin "P$Y2") (pinfunction "VDDH_P$Y2") (pintype "power_in"))
    )
    (net (code "7") (name "ALERT") (class "Default")
      (node (ref "U1") (pin "P$J24") (pinfunction "P0.10/NFC2_P$J24") (pintype "bidirectional"))
      (node (ref "U3") (pin "5") (pinfunction "~{ALERT}_5") (pintype "output"))
    )
    (net (code "8") (name "D+") (class "Default")
      (node (ref "D3") (pin "4") (pinfunction "I/O2_2_4") (pintype "bidirectional"))
      (node (ref "U1") (pin "P$AD6") (pinfunction "D+_P$AD6") (pintype "bidirectional"))
    )
    (net (code "9") (name "D-") (class "Default")
      (node (ref "D3") (pin "6") (pinfunction "I/O1_2_6") (pintype "bidirectional"))
      (node (ref "U1") (pin "P$AD4") (pinfunction "D-_P$AD4") (pintype "bidirectional"))
    )
    (net (code "10") (name "DN") (class "Default")
      (node (ref "D3") (pin "1") (pinfunction "I/O1_1_1") (pintype "bidirectional"))
      (node (ref "J4") (pin "A7") (pinfunction "DN1_A7") (pintype "bidirectional"))
      (node (ref "J4") (pin "B7") (pinfunction "DN2_B7") (pintype "bidirectional"))
    )
    (net (code "11") (name "DP") (class "Default")
      (node (ref "D3") (pin "3") (pinfunction "I/O2_1_3") (pintype "bidirectional"))
      (node (ref "J4") (pin "A6") (pinfunction "DP1_A6") (pintype "bidirectional"))
      (node (ref "J4") (pin "B6") (pinfunction "DP2_B6") (pintype "bidirectional"))
    )
    (net (code "12") (name "EPD_3V3") (class "Default")
      (node (ref "C1-EP-DR") (pin "1") (pinfunction "1_1") (pintype "passive"))
      (node (ref "EPD_C5") (pin "2") (pinfunction "2_2") (pintype "passive"))
      (node (ref "J1") (pin "15") (pinfunction "15_15") (pintype "bidirectional"))
      (node (ref "J1") (pin "16") (pinfunction "16_16") (pintype "bidirectional"))
      (node (ref "L5") (pin "2") (pinfunction "2_2") (pintype "passive"))
      (node (ref "Q1") (pin "3") (pinfunction "D_3") (pintype "bidirectional"))
    )
    (net (code "13") (name "EPD_BUSY") (class "Default")
      (node (ref "J1") (pin "9") (pinfunction "9_9") (pintype "bidirectional"))
      (node (ref "U1") (pin "P$AD12") (pinfunction "P0.17_P$AD12") (pintype "bidirectional"))
    )
    (net (code "14") (name "EPD_CS") (class "Default")
      (node (ref "J1") (pin "12") (pinfunction "12_12") (pintype "bidirectional"))
      (node (ref "U1") (pin "P$K2") (pinfunction "P0.05/AIN3_P$K2") (pintype "bidirectional"))
    )
    (net (code "15") (name "EPD_DC") (class "Default")
      (node (ref "J1") (pin "11") (pinfunction "11_11") (pintype "bidirectional"))
      (node (ref "U1") (pin "P$AD10") (pinfunction "P0.15_P$AD10") (pintype "bidirectional"))
    )
    (net (code "16") (name "EPD_RST") (class "Default")
      (node (ref "J1") (pin "10") (pinfunction "10_10") (pintype "bidirectional"))
      (node (ref "U1") (pin "P$AC11") (pinfunction "P0.16_P$AC11") (pintype "bidirectional"))
    )
    (net (code "17") (name "GDR") (class "Default")
      (node (ref "J1") (pin "2") (pinfunction "2_2") (pintype "bidirectional"))
      (node (ref "Q3") (pin "1") (pinfunction "G_1") (pintype "bidirectional"))
      (node (ref "R2_EP_DR") (pin "2") (pinfunction "2_2") (pintype "bidirectional"))
    )
    (net (code "18") (name "GND") (class "Default")
      (node (ref "C1") (pin "2") (pinfunction "2_2") (pintype "passive"))
      (node (ref "C1-EP-DR") (pin "2") (pinfunction "2_2") (pintype "passive"))
      (node (ref "C10") (pin "2") (pinfunction "2_2") (pintype "passive"))
      (node (ref "C11") (pin "2") (pinfunction "2_2") (pintype "passive"))
      (node (ref "C12") (pin "2") (pinfunction "2_2") (pintype "passive"))
      (node (ref "C13") (pin "2") (pinfunction "2_2") (pintype "passive"))
      (node (ref "C14") (pin "2") (pinfunction "2_2") (pintype "passive"))
      (node (ref "C15") (pin "2") (pinfunction "2_2") (pintype "passive"))
      (node (ref "C16") (pin "2") (pinfunction "2_2") (pintype "passive"))
      (node (ref "C17") (pin "1") (pinfunction "1_1") (pintype "passive"))
      (node (ref "C18") (pin "1") (pinfunction "1_1") (pintype "passive"))
      (node (ref "C19") (pin "1") (pinfunction "1_1") (pintype "passive"))
      (node (ref "C2") (pin "2") (pinfunction "2_2") (pintype "passive"))
      (node (ref "C20") (pin "2") (pinfunction "2_2") (pintype "passive"))
      (node (ref "C21") (pin "2") (pinfunction "2_2") (pintype "passive"))
      (node (ref "C22") (pin "2") (pinfunction "2_2") (pintype "passive"))
      (node (ref "C23") (pin "1") (pinfunction "1_1") (pintype "passive"))
      (node (ref "C24") (pin "1") (pinfunction "1_1") (pintype "passive"))
      (node (ref "C25") (pin "2") (pinfunction "2_2") (pintype "passive"))
      (node (ref "C27") (pin "1") (pinfunction "1_1") (pintype "passive"))
      (node (ref "C29") (pin "1") (pinfunction "1_1") (pintype "passive"))
      (node (ref "C3") (pin "2") (pinfunction "2_2") (pintype "passive"))
      (node (ref "C30") (pin "1") (pinfunction "1_1") (pintype "passive"))
      (node (ref "C31") (pin "1") (pinfunction "1_1") (pintype "passive"))
      (node (ref "C32") (pin "1") (pinfunction "1_1") (pintype "passive"))
      (node (ref "C33") (pin "2") (pinfunction "2_2") (pintype "passive"))
      (node (ref "C34") (pin "1") (pinfunction "1_1") (pintype "passive"))
      (node (ref "C37") (pin "1") (pinfunction "1_1") (pintype "passive"))
      (node (ref "C38") (pin "1") (pinfunction "1_1") (pintype "passive"))
      (node (ref "C39") (pin "2") (pinfunction "2_2") (pintype "passive"))
      (node (ref "C4") (pin "2") (pinfunction "2_2") (pintype "passive"))
      (node (ref "C42") (pin "2") (pinfunction "2_2") (pintype "passive"))
      (node (ref "C43") (pin "2") (pinfunction "2_2") (pintype "passive"))
      (node (ref "C5") (pin "2") (pinfunction "2_2") (pintype "passive"))
      (node (ref "C6") (pin "2") (pinfunction "2_2") (pintype "passive"))
      (node (ref "C7") (pin "2") (pinfunction "2_2") (pintype "passive"))
      (node (ref "C8") (pin "2") (pinfunction "2_2") (pintype "passive"))
      (node (ref "C9") (pin "2") (pinfunction "2_2") (pintype "passive"))
      (node (ref "D3") (pin "2") (pinfunction "GND_2") (pintype "bidirectional"))
      (node (ref "D4") (pin "1") (pinfunction "K_1") (pintype "bidirectional"))
      (node (ref "EPD_C1") (pin "1") (pinfunction "1_1") (pintype "passive"))
      (node (ref "EPD_C10") (pin "1") (pinfunction "1_1") (pintype "passive"))
      (node (ref "EPD_C11") (pin "1") (pinfunction "1_1") (pintype "passive"))
      (node (ref "EPD_C12") (pin "1") (pinfunction "1_1") (pintype "passive"))
      (node (ref "EPD_C2") (pin "1") (pinfunction "1_1") (pintype "passive"))
      (node (ref "EPD_C5") (pin "1") (pinfunction "1_1") (pintype "passive"))
      (node (ref "EPD_C6") (pin "1") (pinfunction "1_1") (pintype "passive"))
      (node (ref "EPD_C7") (pin "1") (pinfunction "1_1") (pintype "passive"))
      (node (ref "EPD_C8") (pin "1") (pinfunction "1_1") (pintype "passive"))
      (node (ref "EPD_C9") (pin "1") (pinfunction "1_1") (pintype "passive"))
      (node (ref "IC1") (pin "D2") (pinfunction "GND_D2") (pintype "bidirectional"))
      (node (ref "IC2") (pin "B1") (pinfunction "IN/TRIG_B1") (pintype "bidirectional"))
      (node (ref "IC2") (pin "B3") (pinfunction "GND_B3") (pintype "bidirectional"))
      (node (ref "IC3") (pin "8") (pinfunction "GNDIO_8") (pintype "bidirectional"))
      (node (ref "IC3") (pin "9") (pinfunction "GND_9") (pintype "bidirectional"))
      (node (ref "IC9") (pin "B1") (pinfunction "VSEL_B1") (pintype "bidirectional"))
      (node (ref "IC9") (pin "C1") (pinfunction "AGND_C1") (pintype "bidirectional"))
      (node (ref "IC9") (pin "C2") (pinfunction "PGND_1_C2") (pintype "bidirectional"))
      (node (ref "IC9") (pin "C3") (pinfunction "PGND_2_C3") (pintype "bidirectional"))
      (node (ref "J1") (pin "17") (pinfunction "17_17") (pintype "bidirectional"))
      (node (ref "J1") (pin "8") (pinfunction "8_8") (pintype "bidirectional"))
      (node (ref "J1") (pin "MP1") (pinfunction "MP1_MP1") (pintype "bidirectional"))
      (node (ref "J1") (pin "MP2") (pinfunction "MP2_MP2") (pintype "bidirectional"))
      (node (ref "J2") (pin "3") (pinfunction "3_3") (pintype "bidirectional"))
      (node (ref "J2") (pin "5") (pinfunction "5_5") (pintype "bidirectional"))
      (node (ref "J4") (pin "A12_B1") (pinfunction "GND_A12_B1") (pintype "power_in"))
      (node (ref "J4") (pin "A1_B12") (pinfunction "GND_A1_B12") (pintype "power_in"))
      (node (ref "J4") (pin "SH1") (pinfunction "SHIELD_SH1") (pintype "passive"))
      (node (ref "J4") (pin "SH2") (pinfunction "SHIELD_SH2") (pintype "passive"))
      (node (ref "J4") (pin "SH3") (pinfunction "SHIELD_SH3") (pintype "passive"))
      (node (ref "J4") (pin "SH4") (pinfunction "SHIELD_SH4") (pintype "passive"))
      (node (ref "R1_USB") (pin "1") (pinfunction "1_1") (pintype "bidirectional"))
      (node (ref "R2_EP_DR") (pin "1") (pinfunction "1_1") (pintype "bidirectional"))
      (node (ref "R2_USB") (pin "2") (pinfunction "2_2") (pintype "bidirectional"))
      (node (ref "R3") (pin "1") (pinfunction "1_1") (pintype "bidirectional"))
      (node (ref "R9") (pin "1") (pinfunction "1_1") (pintype "bidirectional"))
      (node (ref "R_TYPE_SEL") (pin "1") (pinfunction "1_1") (pintype "bidirectional"))
      (node (ref "SJ1") (pin "1") (pinfunction "1_1") (pintype "passive"))
      (node (ref "SW_DN") (pin "1") (pinfunction "1_1") (pintype "passive"))
      (node (ref "SW_ENT") (pin "1") (pinfunction "1_1") (pintype "passive"))
      (node (ref "SW_UP") (pin "1") (pinfunction "1_1") (pintype "passive"))
      (node (ref "TP_BAT_GND") (pin "TP") (pinfunction "TP_TP") (pintype "input"))
      (node (ref "TP_GND") (pin "TP") (pinfunction "TP_TP") (pintype "input"))
      (node (ref "U1") (pin "P$74") (pinfunction "VSS_PAD_P$74") (pintype "bidirectional"))
      (node (ref "U1") (pin "P$75") (pinfunction "VSS_PAD_P$75") (pintype "bidirectional"))
      (node (ref "U1") (pin "P$76") (pinfunction "VSS_PAD_P$76") (pintype "bidirectional"))
      (node (ref "U1") (pin "P$77") (pinfunction "VSS_PAD_P$77") (pintype "bidirectional"))
      (node (ref "U1") (pin "P$78") (pinfunction "VSS_PAD_P$78") (pintype "bidirectional"))
      (node (ref "U1") (pin "P$79") (pinfunction "VSS_PAD_P$79") (pintype "bidirectional"))
      (node (ref "U1") (pin "P$80") (pinfunction "VSS_PAD_P$80") (pintype "bidirectional"))
      (node (ref "U1") (pin "P$81") (pinfunction "VSS_PAD_P$81") (pintype "bidirectional"))
      (node (ref "U1") (pin "P$82") (pinfunction "VSS_PAD_P$82") (pintype "bidirectional"))
      (node (ref "U1") (pin "P$83") (pinfunction "VSS_PAD_P$83") (pintype "bidirectional"))
      (node (ref "U1") (pin "P$84") (pinfunction "VSS_PAD_P$84") (pintype "bidirectional"))
      (node (ref "U1") (pin "P$85") (pinfunction "VSS_PAD_P$85") (pintype "bidirectional"))
      (node (ref "U1") (pin "P$86") (pinfunction "VSS_PAD_P$86") (pintype "bidirectional"))
      (node (ref "U1") (pin "P$87") (pinfunction "VSS_PAD_P$87") (pintype "bidirectional"))
      (node (ref "U1") (pin "P$88") (pinfunction "VSS_PAD_P$88") (pintype "bidirectional"))
      (node (ref "U1") (pin "P$89") (pinfunction "VSS_PAD_P$89") (pintype "bidirectional"))
      (node (ref "U1") (pin "P$90") (pinfunction "VSS_PAD_P$90") (pintype "bidirectional"))
      (node (ref "U1") (pin "P$B7") (pinfunction "VSS_P$B7") (pintype "power_in"))
      (node (ref "U1") (pin "P$F23") (pinfunction "VSS_PA_P$F23") (pintype "bidirectional"))
      (node (ref "U3") (pin "1") (pinfunction "CTG_1") (pintype "power_in"))
      (node (ref "U3") (pin "4") (pinfunction "GND_4") (pintype "power_in"))
      (node (ref "U3") (pin "6") (pinfunction "QSTRT_6") (pintype "input"))
      (node (ref "U3") (pin "9") (pinfunction "EP_9") (pintype "power_in"))
      (node (ref "X1") (pin "2") (pinfunction "2_2") (pintype "passive"))
      (node (ref "X1") (pin "4") (pinfunction "4_4") (pintype "passive"))
    )
    (net (code "19") (name "HAPTIC_EN") (class "Default")
      (node (ref "IC2") (pin "A1") (pinfunction "EN_A1") (pintype "bidirectional"))
      (node (ref "U1") (pin "P$U1") (pinfunction "P0.12_P$U1") (pintype "bidirectional"))
    )
    (net (code "20") (name "IMU_INT1") (class "Default")
      (node (ref "IC3") (pin "5") (pinfunction "INT1_5") (pintype "bidirectional"))
      (node (ref "U1") (pin "P$N1") (pinfunction "P0.08_P$N1") (pintype "bidirectional"))
    )
    (net (code "21") (name "IMU_INT2") (class "Default")
      (node (ref "IC3") (pin "6") (pinfunction "INT2_6") (pintype "bidirectional"))
      (node (ref "U1") (pin "P$P2") (pinfunction "P1.08_P$P2") (pintype "bidirectional"))
    )
    (net (code "22") (name "LX1") (class "Default")
      (node (ref "IC9") (pin "B2") (pinfunction "SW1_1_B2") (pintype "bidirectional"))
      (node (ref "IC9") (pin "B3") (pinfunction "SW1_2_B3") (pintype "bidirectional"))
      (node (ref "L7") (pin "1") (pinfunction "1_1") (pintype "bidirectional"))
    )
    (net (code "23") (name "LX2") (class "Default")
      (node (ref "IC9") (pin "D2") (pinfunction "SW2_1_D2") (pintype "bidirectional"))
      (node (ref "IC9") (pin "D3") (pinfunction "SW2_2_D3") (pintype "bidirectional"))
      (node (ref "L7") (pin "2") (pinfunction "2_2") (pintype "bidirectional"))
    )
    (net (code "24") (name "MOSI") (class "Default")
      (node (ref "J1") (pin "14") (pinfunction "14_14") (pintype "bidirectional"))
      (node (ref "U1") (pin "P$B13") (pinfunction "P0.03/AIN1_P$B13") (pintype "bidirectional"))
    )
    (net (code "25") (name "Net-(D2-K)") (class "Default")
      (node (ref "C2-EP-DR") (pin "1") (pinfunction "1_1") (pintype "passive"))
      (node (ref "D2") (pin "1") (pinfunction "K_1") (pintype "bidirectional"))
      (node (ref "D4") (pin "2") (pinfunction "A_2") (pintype "bidirectional"))
    )
    (net (code "26") (name "Net-(D5-A)") (class "Default")
      (node (ref "C2-EP-DR") (pin "2") (pinfunction "2_2") (pintype "passive"))
      (node (ref "D5") (pin "2") (pinfunction "A_2") (pintype "bidirectional"))
      (node (ref "L5") (pin "1") (pinfunction "1_1") (pintype "passive"))
      (node (ref "Q3") (pin "3") (pinfunction "D_3") (pintype "bidirectional"))
    )
    (net (code "27") (name "Net-(EPD_C1-Pad2)") (class "Default")
      (node (ref "EPD_C1") (pin "2") (pinfunction "2_2") (pintype "passive"))
      (node (ref "J1") (pin "5") (pinfunction "5_5") (pintype "bidirectional"))
    )
    (net (code "28") (name "Net-(EPD_C2-Pad2)") (class "Default")
      (node (ref "EPD_C2") (pin "2") (pinfunction "2_2") (pintype "passive"))
      (node (ref "J1") (pin "4") (pinfunction "4_4") (pintype "bidirectional"))
    )
    (net (code "29") (name "Net-(EPD_C6-Pad2)") (class "Default")
      (node (ref "EPD_C6") (pin "2") (pinfunction "2_2") (pintype "passive"))
      (node (ref "J1") (pin "18") (pinfunction "18_18") (pintype "bidirectional"))
    )
    (net (code "30") (name "Net-(EPD_C7-Pad2)") (class "Default")
      (node (ref "EPD_C7") (pin "2") (pinfunction "2_2") (pintype "passive"))
      (node (ref "J1") (pin "19") (pinfunction "19_19") (pintype "bidirectional"))
    )
    (net (code "31") (name "Net-(EPD_C8-Pad2)") (class "Default")
      (node (ref "EPD_C8") (pin "2") (pinfunction "2_2") (pintype "passive"))
      (node (ref "J1") (pin "20") (pinfunction "20_20") (pintype "bidirectional"))
    )
    (net (code "32") (name "Net-(EPD_C10-Pad2)") (class "Default")
      (node (ref "EPD_C10") (pin "2") (pinfunction "2_2") (pintype "passive"))
      (node (ref "J1") (pin "22") (pinfunction "22_22") (pintype "bidirectional"))
    )
    (net (code "33") (name "Net-(EPD_C12-Pad2)") (class "Default")
      (node (ref "EPD_C12") (pin "2") (pinfunction "2_2") (pintype "passive"))
      (node (ref "J1") (pin "24") (pinfunction "24_24") (pintype "bidirectional"))
    )
    (net (code "34") (name "Net-(IC1-TS{slash}MR)") (class "Default")
      (node (ref "IC1") (pin "D1") (pinfunction "TS/MR_D1") (pintype "bidirectional"))
      (node (ref "R9") (pin "2") (pinfunction "2_2") (pintype "bidirectional"))
    )
    (net (code "35") (name "Net-(IC2-REG)") (class "Default")
      (node (ref "C32") (pin "2") (pinfunction "2_2") (pintype "passive"))
      (node (ref "IC2") (pin "A2") (pinfunction "REG_A2") (pintype "bidirectional"))
    )
    (net (code "36") (name "Net-(IC3-SDO)") (class "Default")
      (node (ref "IC3") (pin "1") (pinfunction "SDO_1") (pintype "bidirectional"))
      (node (ref "R3") (pin "2") (pinfunction "2_2") (pintype "bidirectional"))
    )
    (net (code "37") (name "Net-(IC9-SCL)") (class "Default")
      (node (ref "IC9") (pin "D1") (pinfunction "SCL_D1") (pintype "bidirectional"))
      (node (ref "R4") (pin "2") (pinfunction "2_2") (pintype "bidirectional"))
    )
    (net (code "38") (name "Net-(IC9-SDA)") (class "Default")
      (node (ref "IC9") (pin "E1") (pinfunction "SDA_E1") (pintype "bidirectional"))
      (node (ref "R2") (pin "2") (pinfunction "2_2") (pintype "bidirectional"))
    )
    (net (code "39") (name "Net-(J4-CC1)") (class "Default")
      (node (ref "J4") (pin "A5") (pinfunction "CC1_A5") (pintype "bidirectional"))
      (node (ref "R1_USB") (pin "2") (pinfunction "2_2") (pintype "bidirectional"))
    )
    (net (code "40") (name "Net-(J4-CC2)") (class "Default")
      (node (ref "J4") (pin "B5") (pinfunction "CC2_B5") (pintype "bidirectional"))
      (node (ref "R2_USB") (pin "1") (pinfunction "1_1") (pintype "bidirectional"))
    )
    (net (code "41") (name "Net-(L2-Pad2)") (class "Default")
      (node (ref "L2") (pin "2") (pinfunction "2_2") (pintype "passive"))
      (node (ref "L3") (pin "1") (pinfunction "1_1") (pintype "passive"))
    )
    (net (code "42") (name "Net-(R1_EP_DR-Pad1)") (class "Default")
      (node (ref "R1_EP_DR") (pin "1") (pinfunction "1_1") (pintype "bidirectional"))
      (node (ref "R_TYPE_SEL") (pin "2") (pinfunction "2_2") (pintype "bidirectional"))
      (node (ref "SJ1") (pin "2") (pinfunction "2_2") (pintype "passive"))
    )
    (net (code "43") (name "Net-(U1-ANT)") (class "Default")
      (node (ref "C3") (pin "1") (pinfunction "1_1") (pintype "passive"))
      (node (ref "L1") (pin "1") (pinfunction "1_1") (pintype "passive"))
      (node (ref "U1") (pin "P$H23") (pinfunction "ANT_P$H23") (pintype "bidirectional"))
    )
    (net (code "44") (name "Net-(U1-DCC)") (class "Default")
      (node (ref "L2") (pin "1") (pinfunction "1_1") (pintype "passive"))
      (node (ref "U1") (pin "P$B3") (pinfunction "DCC_P$B3") (pintype "output"))
    )
    (net (code "45") (name "Net-(U1-DEC1)") (class "Default")
      (node (ref "C5") (pin "1") (pinfunction "1_1") (pintype "passive"))
      (node (ref "U1") (pin "P$C1") (pinfunction "DEC1_P$C1") (pintype "power_in"))
    )
    (net (code "46") (name "Net-(U1-DEC2)") (class "Default")
      (node (ref "C13") (pin "1") (pinfunction "1_1") (pintype "passive"))
      (node (ref "U1") (pin "P$A18") (pinfunction "DEC2_P$A18") (pintype "bidirectional"))
    )
    (net (code "47") (name "Net-(U1-DEC3V3)") (class "Default")
      (node (ref "C20") (pin "1") (pinfunction "1_1") (pintype "passive"))
      (node (ref "U1") (pin "P$AC5") (pinfunction "DEC3V3_P$AC5") (pintype "bidirectional"))
    )
    (net (code "48") (name "Net-(U1-DEC5)") (class "Default")
      (node (ref "C9") (pin "1") (pinfunction "1_1") (pintype "passive"))
      (node (ref "U1") (pin "P$N24") (pinfunction "DEC5_P$N24") (pintype "bidirectional"))
    )
    (net (code "49") (name "Net-(U1-XC1)") (class "Default")
      (node (ref "C1") (pin "1") (pinfunction "1_1") (pintype "passive"))
      (node (ref "U1") (pin "P$B24") (pinfunction "XC1_P$B24") (pintype "input"))
      (node (ref "X1") (pin "1") (pinfunction "1_1") (pintype "passive"))
    )
    (net (code "50") (name "Net-(U1-XC2)") (class "Default")
      (node (ref "C2") (pin "1") (pinfunction "1_1") (pintype "passive"))
      (node (ref "U1") (pin "P$A23") (pinfunction "XC2_P$A23") (pintype "output"))
      (node (ref "X1") (pin "3") (pinfunction "3_3") (pintype "passive"))
    )
    (net (code "51") (name "OUT+") (class "Default")
      (node (ref "IC2") (pin "A3") (pinfunction "OUT+_A3") (pintype "bidirectional"))
      (node (ref "TP_OP") (pin "TP") (pinfunction "TP_TP") (pintype "input"))
    )
    (net (code "52") (name "OUT-") (class "Default")
      (node (ref "IC2") (pin "C3") (pinfunction "OUT-_C3") (pintype "bidirectional"))
      (node (ref "TP_ON") (pin "TP") (pinfunction "TP_TP") (pintype "input"))
    )
    (net (code "53") (name "P0.04") (class "Default")
      (node (ref "U1") (pin "P$J1") (pinfunction "P0.04/AIN2_P$J1") (pintype "bidirectional"))
    )
    (net (code "54") (name "P0.09") (class "Default")
      (node (ref "U1") (pin "P$L24") (pinfunction "P0.09/NFC1_P$L24") (pintype "bidirectional"))
    )
    (net (code "55") (name "P0.13") (class "Default")
      (node (ref "C30") (pin "2") (pinfunction "2_2") (pintype "passive"))
      (node (ref "R5") (pin "1") (pinfunction "1_1") (pintype "bidirectional"))
      (node (ref "SW_UP") (pin "2") (pinfunction "2_2") (pintype "passive"))
      (node (ref "U1") (pin "P$AD8") (pinfunction "P0.13_P$AD8") (pintype "bidirectional"))
    )
    (net (code "56") (name "P0.14") (class "Default")
      (node (ref "C31") (pin "2") (pinfunction "2_2") (pintype "passive"))
      (node (ref "R8") (pin "1") (pinfunction "1_1") (pintype "bidirectional"))
      (node (ref "SW_ENT") (pin "2") (pinfunction "2_2") (pintype "passive"))
      (node (ref "U1") (pin "P$AC9") (pinfunction "P0.14_P$AC9") (pintype "bidirectional"))
    )
    (net (code "57") (name "P0.19") (class "Default")
      (node (ref "U1") (pin "P$AC15") (pinfunction "P0.19_P$AC15") (pintype "bidirectional"))
    )
    (net (code "58") (name "P0.20") (class "Default")
      (node (ref "U1") (pin "P$AD16") (pinfunction "P0.20_P$AD16") (pintype "bidirectional"))
    )
    (net (code "59") (name "P0.21") (class "Default")
      (node (ref "U1") (pin "P$AC17") (pinfunction "P0.21_P$AC17") (pintype "bidirectional"))
    )
    (net (code "60") (name "P0.22") (class "Default")
      (node (ref "U1") (pin "P$AD18") (pinfunction "P0.22_P$AD18") (pintype "bidirectional"))
    )
    (net (code "61") (name "P0.23") (class "Default")
      (node (ref "U1") (pin "P$AC19") (pinfunction "P0.23_P$AC19") (pintype "bidirectional"))
    )
    (net (code "62") (name "P0.24") (class "Default")
      (node (ref "U1") (pin "P$AD20") (pinfunction "P0.24_P$AD20") (pintype "bidirectional"))
    )
    (net (code "63") (name "P0.25") (class "Default")
      (node (ref "U1") (pin "P$AC21") (pinfunction "P0.25_P$AC21") (pintype "bidirectional"))
    )
    (net (code "64") (name "P0.26") (class "Default")
      (node (ref "U1") (pin "P$G1") (pinfunction "P0.26_P$G1") (pintype "bidirectional"))
    )
    (net (code "65") (name "P0.27") (class "Default")
      (node (ref "U1") (pin "P$H2") (pinfunction "P0.27_P$H2") (pintype "bidirectional"))
    )
    (net (code "66") (name "P0.28") (class "Default")
      (node (ref "U1") (pin "P$B11") (pinfunction "P0.28/AIN4_P$B11") (pintype "bidirectional"))
    )
    (net (code "67") (name "P0.29") (class "Default")
      (node (ref "U1") (pin "P$A10") (pinfunction "P0.29/AIN5_P$A10") (pintype "bidirectional"))
    )
    (net (code "68") (name "P0.30") (class "Default")
      (node (ref "U1") (pin "P$B9") (pinfunction "P0.30/AIN6_P$B9") (pintype "bidirectional"))
    )
    (net (code "69") (name "P0.31") (class "Default")
      (node (ref "U1") (pin "P$A8") (pinfunction "P0.31/AIN7_P$A8") (pintype "bidirectional"))
    )
    (net (code "70") (name "P1.01") (class "Default")
      (node (ref "Q1") (pin "1") (pinfunction "G_1") (pintype "bidirectional"))
      (node (ref "R_PWR_EPD") (pin "1") (pinfunction "1_1") (pintype "bidirectional"))
      (node (ref "U1") (pin "P$Y23") (pinfunction "P1.01_P$Y23") (pintype "bidirectional"))
    )
    (net (code "71") (name "P1.02") (class "Default")
      (node (ref "C29") (pin "2") (pinfunction "2_2") (pintype "passive"))
      (node (ref "R7") (pin "1") (pinfunction "1_1") (pintype "bidirectional"))
      (node (ref "SW_DN") (pin "2") (pinfunction "2_2") (pintype "passive"))
      (node (ref "U1") (pin "P$W24") (pinfunction "P1.02_P$W24") (pintype "bidirectional"))
    )
    (net (code "72") (name "P1.03") (class "Default")
      (node (ref "U1") (pin "P$V23") (pinfunction "P1.03_P$V23") (pintype "bidirectional"))
    )
    (net (code "73") (name "P1.04") (class "Default")
      (node (ref "U1") (pin "P$U24") (pinfunction "P1.04_P$U24") (pintype "bidirectional"))
    )
    (net (code "74") (name "P1.05") (class "Default")
      (node (ref "U1") (pin "P$T23") (pinfunction "P1.05_P$T23") (pintype "bidirectional"))
    )
    (net (code "75") (name "P1.06") (class "Default")
      (node (ref "U1") (pin "P$R24") (pinfunction "P1.06_P$R24") (pintype "bidirectional"))
    )
    (net (code "76") (name "P1.07") (class "Default")
      (node (ref "U1") (pin "P$P23") (pinfunction "P1.07_P$P23") (pintype "bidirectional"))
    )
    (net (code "77") (name "P1.09") (class "Default")
      (node (ref "U1") (pin "P$R1") (pinfunction "P1.09_P$R1") (pintype "bidirectional"))
    )
    (net (code "78") (name "P1.10") (class "Default")
      (node (ref "U1") (pin "P$A20") (pinfunction "P1.10_P$A20") (pintype "bidirectional"))
    )
    (net (code "79") (name "P1.11") (class "Default")
      (node (ref "U1") (pin "P$B19") (pinfunction "P1.11_P$B19") (pintype "bidirectional"))
    )
    (net (code "80") (name "P1.12") (class "Default")
      (node (ref "U1") (pin "P$B17") (pinfunction "P1.12_P$B17") (pintype "bidirectional"))
    )
    (net (code "81") (name "P1.13") (class "Default")
      (node (ref "U1") (pin "P$A16") (pinfunction "P1.13_P$A16") (pintype "bidirectional"))
    )
    (net (code "82") (name "P1.14") (class "Default")
      (node (ref "U1") (pin "P$B15") (pinfunction "P1.14_P$B15") (pintype "bidirectional"))
    )
    (net (code "83") (name "P1.15") (class "Default")
      (node (ref "U1") (pin "P$A14") (pinfunction "P1.15_P$A14") (pintype "bidirectional"))
    )
    (net (code "84") (name "PMIC_INT") (class "Default")
      (node (ref "IC1") (pin "A1") (pinfunction "~{INT}_A1") (pintype "bidirectional"))
      (node (ref "U1") (pin "P$T2") (pinfunction "P0.11_P$T2") (pintype "bidirectional"))
    )
    (net (code "85") (name "PREVGH") (class "Default")
      (node (ref "D5") (pin "1") (pinfunction "K_1") (pintype "bidirectional"))
      (node (ref "EPD_C9") (pin "2") (pinfunction "2_2") (pintype "passive"))
      (node (ref "J1") (pin "21") (pinfunction "21_21") (pintype "bidirectional"))
    )
    (net (code "86") (name "PREVGL") (class "Default")
      (node (ref "D2") (pin "2") (pinfunction "A_2") (pintype "bidirectional"))
      (node (ref "EPD_C11") (pin "2") (pinfunction "2_2") (pintype "passive"))
      (node (ref "J1") (pin "23") (pinfunction "23_23") (pintype "bidirectional"))
    )
    (net (code "87") (name "RESE") (class "Default")
      (node (ref "J1") (pin "3") (pinfunction "3_3") (pintype "bidirectional"))
      (node (ref "Q3") (pin "2") (pinfunction "S_2") (pintype "bidirectional"))
      (node (ref "R1_EP_DR") (pin "2") (pinfunction "2_2") (pintype "bidirectional"))
    )
    (net (code "88") (name "RESET") (class "Default")
      (node (ref "J2") (pin "6") (pinfunction "6_6") (pintype "bidirectional"))
      (node (ref "TP_RESET") (pin "TP") (pinfunction "TP_TP") (pintype "input"))
      (node (ref "U1") (pin "P$AC13") (pinfunction "P0.18/RESET_P$AC13") (pintype "bidirectional"))
    )
    (net (code "89") (name "SCK") (class "Default")
      (node (ref "J1") (pin "13") (pinfunction "13_13") (pintype "bidirectional"))
      (node (ref "U1") (pin "P$A12") (pinfunction "P0.02/AIN0_P$A12") (pintype "bidirectional"))
    )
    (net (code "90") (name "SCL") (class "Default")
      (node (ref "IC1") (pin "B1") (pinfunction "SCL_B1") (pintype "bidirectional"))
      (node (ref "IC2") (pin "C1") (pinfunction "SCL_C1") (pintype "bidirectional"))
      (node (ref "IC3") (pin "12") (pinfunction "SCX_12") (pintype "bidirectional"))
      (node (ref "R17") (pin "1") (pinfunction "1_1") (pintype "bidirectional"))
      (node (ref "R4") (pin "1") (pinfunction "1_1") (pintype "bidirectional"))
      (node (ref "TP_SCL") (pin "TP") (pinfunction "TP_TP") (pintype "input"))
      (node (ref "U1") (pin "P$M2") (pinfunction "P0.07_P$M2") (pintype "bidirectional"))
      (node (ref "U3") (pin "7") (pinfunction "SCL_7") (pintype "input"))
    )
    (net (code "91") (name "SDA") (class "Default")
      (node (ref "IC1") (pin "C1") (pinfunction "SDA_C1") (pintype "bidirectional"))
      (node (ref "IC2") (pin "B2") (pinfunction "SDA_B2") (pintype "bidirectional"))
      (node (ref "IC3") (pin "2") (pinfunction "SDX_2") (pintype "bidirectional"))
      (node (ref "R18") (pin "1") (pinfunction "1_1") (pintype "bidirectional"))
      (node (ref "R2") (pin "1") (pinfunction "1_1") (pintype "bidirectional"))
      (node (ref "TP_SDA") (pin "TP") (pinfunction "TP_TP") (pintype "input"))
      (node (ref "U1") (pin "P$L1") (pinfunction "P0.06_P$L1") (pintype "bidirectional"))
      (node (ref "U3") (pin "8") (pinfunction "SDA_8") (pintype "bidirectional"))
    )
    (net (code "92") (name "SWDCLK") (class "Default")
      (node (ref "J2") (pin "4") (pinfunction "4_4") (pintype "bidirectional"))
      (node (ref "TP_SWDCLK") (pin "TP") (pinfunction "TP_TP") (pintype "input"))
      (node (ref "U1") (pin "P$AA24") (pinfunction "SWDCLK_P$AA24") (pintype "input"))
    )
    (net (code "93") (name "SWDIO") (class "Default")
      (node (ref "J2") (pin "2") (pinfunction "2_2") (pintype "bidirectional"))
      (node (ref "TP_SWDIO") (pin "TP") (pinfunction "TP_TP") (pintype "input"))
      (node (ref "U1") (pin "P$AC24") (pinfunction "SWDIO_P$AC24") (pintype "bidirectional"))
    )
    (net (code "94") (name "SWO") (class "Default")
      (node (ref "TP_SWO") (pin "TP") (pinfunction "TP_TP") (pintype "input"))
      (node (ref "U1") (pin "P$AD22") (pinfunction "P1.00_P$AD22") (pintype "bidirectional"))
    )
    (net (code "95") (name "VBAT") (class "Default")
      (node (ref "C27") (pin "2") (pinfunction "2_2") (pintype "passive"))
      (node (ref "C37") (pin "2") (pinfunction "2_2") (pintype "passive"))
      (node (ref "IC1") (pin "C2") (pinfunction "BAT_C2") (pintype "bidirectional"))
      (node (ref "TP_VBAT") (pin "TP") (pinfunction "TP_TP") (pintype "input"))
      (node (ref "U3") (pin "2") (pinfunction "CELL_2") (pintype "power_in"))
      (node (ref "U3") (pin "3") (pinfunction "VDD_3") (pintype "power_in"))
    )
    (net (code "96") (name "VBUS") (class "Default")
      (node (ref "C21") (pin "1") (pinfunction "1_1") (pintype "passive"))
      (node (ref "C38") (pin "2") (pinfunction "2_2") (pintype "passive"))
      (node (ref "C42") (pin "1") (pinfunction "1_1") (pintype "passive"))
      (node (ref "C43") (pin "1") (pinfunction "1_1") (pintype "passive"))
      (node (ref "D3") (pin "5") (pinfunction "VBUS_5") (pintype "bidirectional"))
      (node (ref "IC1") (pin "A2") (pinfunction "IN_A2") (pintype "bidirectional"))
      (node (ref "J4") (pin "A4_B9") (pinfunction "VBUS_A4_B9") (pintype "power_in"))
      (node (ref "J4") (pin "A9_B4") (pinfunction "VBUS_A9_B4") (pintype "power_in"))
      (node (ref "U1") (pin "P$AD2") (pinfunction "VBUS_P$AD2") (pintype "power_in"))
    )
    (net (code "97") (name "VREG") (class "Default")
      (node (ref "C23") (pin "2") (pinfunction "2_2") (pintype "passive"))
      (node (ref "C24") (pin "2") (pinfunction "2_2") (pintype "passive"))
      (node (ref "C39") (pin "1") (pinfunction "1_1") (pintype "passive"))
      (node (ref "IC1") (pin "B2") (pinfunction "SYS_B2") (pintype "bidirectional"))
      (node (ref "IC9") (pin "A1") (pinfunction "EN_A1") (pintype "bidirectional"))
      (node (ref "IC9") (pin "A2") (pinfunction "VIN_1_A2") (pintype "bidirectional"))
      (node (ref "IC9") (pin "A3") (pinfunction "VIN_2_A3") (pintype "bidirectional"))
      (node (ref "TP_VREG") (pin "TP") (pinfunction "TP_TP") (pintype "input"))
    )
    (net (code "98") (name "unconnected-(ANT1-NC-Pad2)") (class "Default")
      (node (ref "ANT1") (pin "2") (pinfunction "NC_2") (pintype "no_connect"))
    )
    (net (code "99") (name "unconnected-(IC3-ASCL-Pad11)") (class "Default")
      (node (ref "IC3") (pin "11") (pinfunction "ASCL_11") (pintype "bidirectional"))
    )
    (net (code "100") (name "unconnected-(IC3-ASDA-Pad4)") (class "Default")
      (node (ref "IC3") (pin "4") (pinfunction "ASDA_4") (pintype "bidirectional"))
    )
    (net (code "101") (name "unconnected-(J1-Pad1)") (class "Default")
      (node (ref "J1") (pin "1") (pinfunction "1_1") (pintype "bidirectional"))
    )
    (net (code "102") (name "unconnected-(J1-Pad6)") (class "Default")
      (node (ref "J1") (pin "6") (pinfunction "6_6") (pintype "bidirectional"))
    )
    (net (code "103") (name "unconnected-(J1-Pad7)") (class "Default")
      (node (ref "J1") (pin "7") (pinfunction "7_7") (pintype "bidirectional"))
    )
    (net (code "104") (name "unconnected-(J4-SBU1-PadA8)") (class "Default")
      (node (ref "J4") (pin "A8") (pinfunction "SBU1_A8") (pintype "bidirectional"))
    )
    (net (code "105") (name "unconnected-(J4-SBU2-PadB8)") (class "Default")
      (node (ref "J4") (pin "B8") (pinfunction "SBU2_B8") (pintype "bidirectional"))
    )
    (net (code "106") (name "unconnected-(U1-DCCH-PadP$AB2)") (class "Default")
      (node (ref "U1") (pin "P$AB2") (pinfunction "DCCH_P$AB2") (pintype "bidirectional"))
    )
  )
)
